# Aq1A_Guppy.net
KiCad netlist of a schematic drawn in Altium Designer
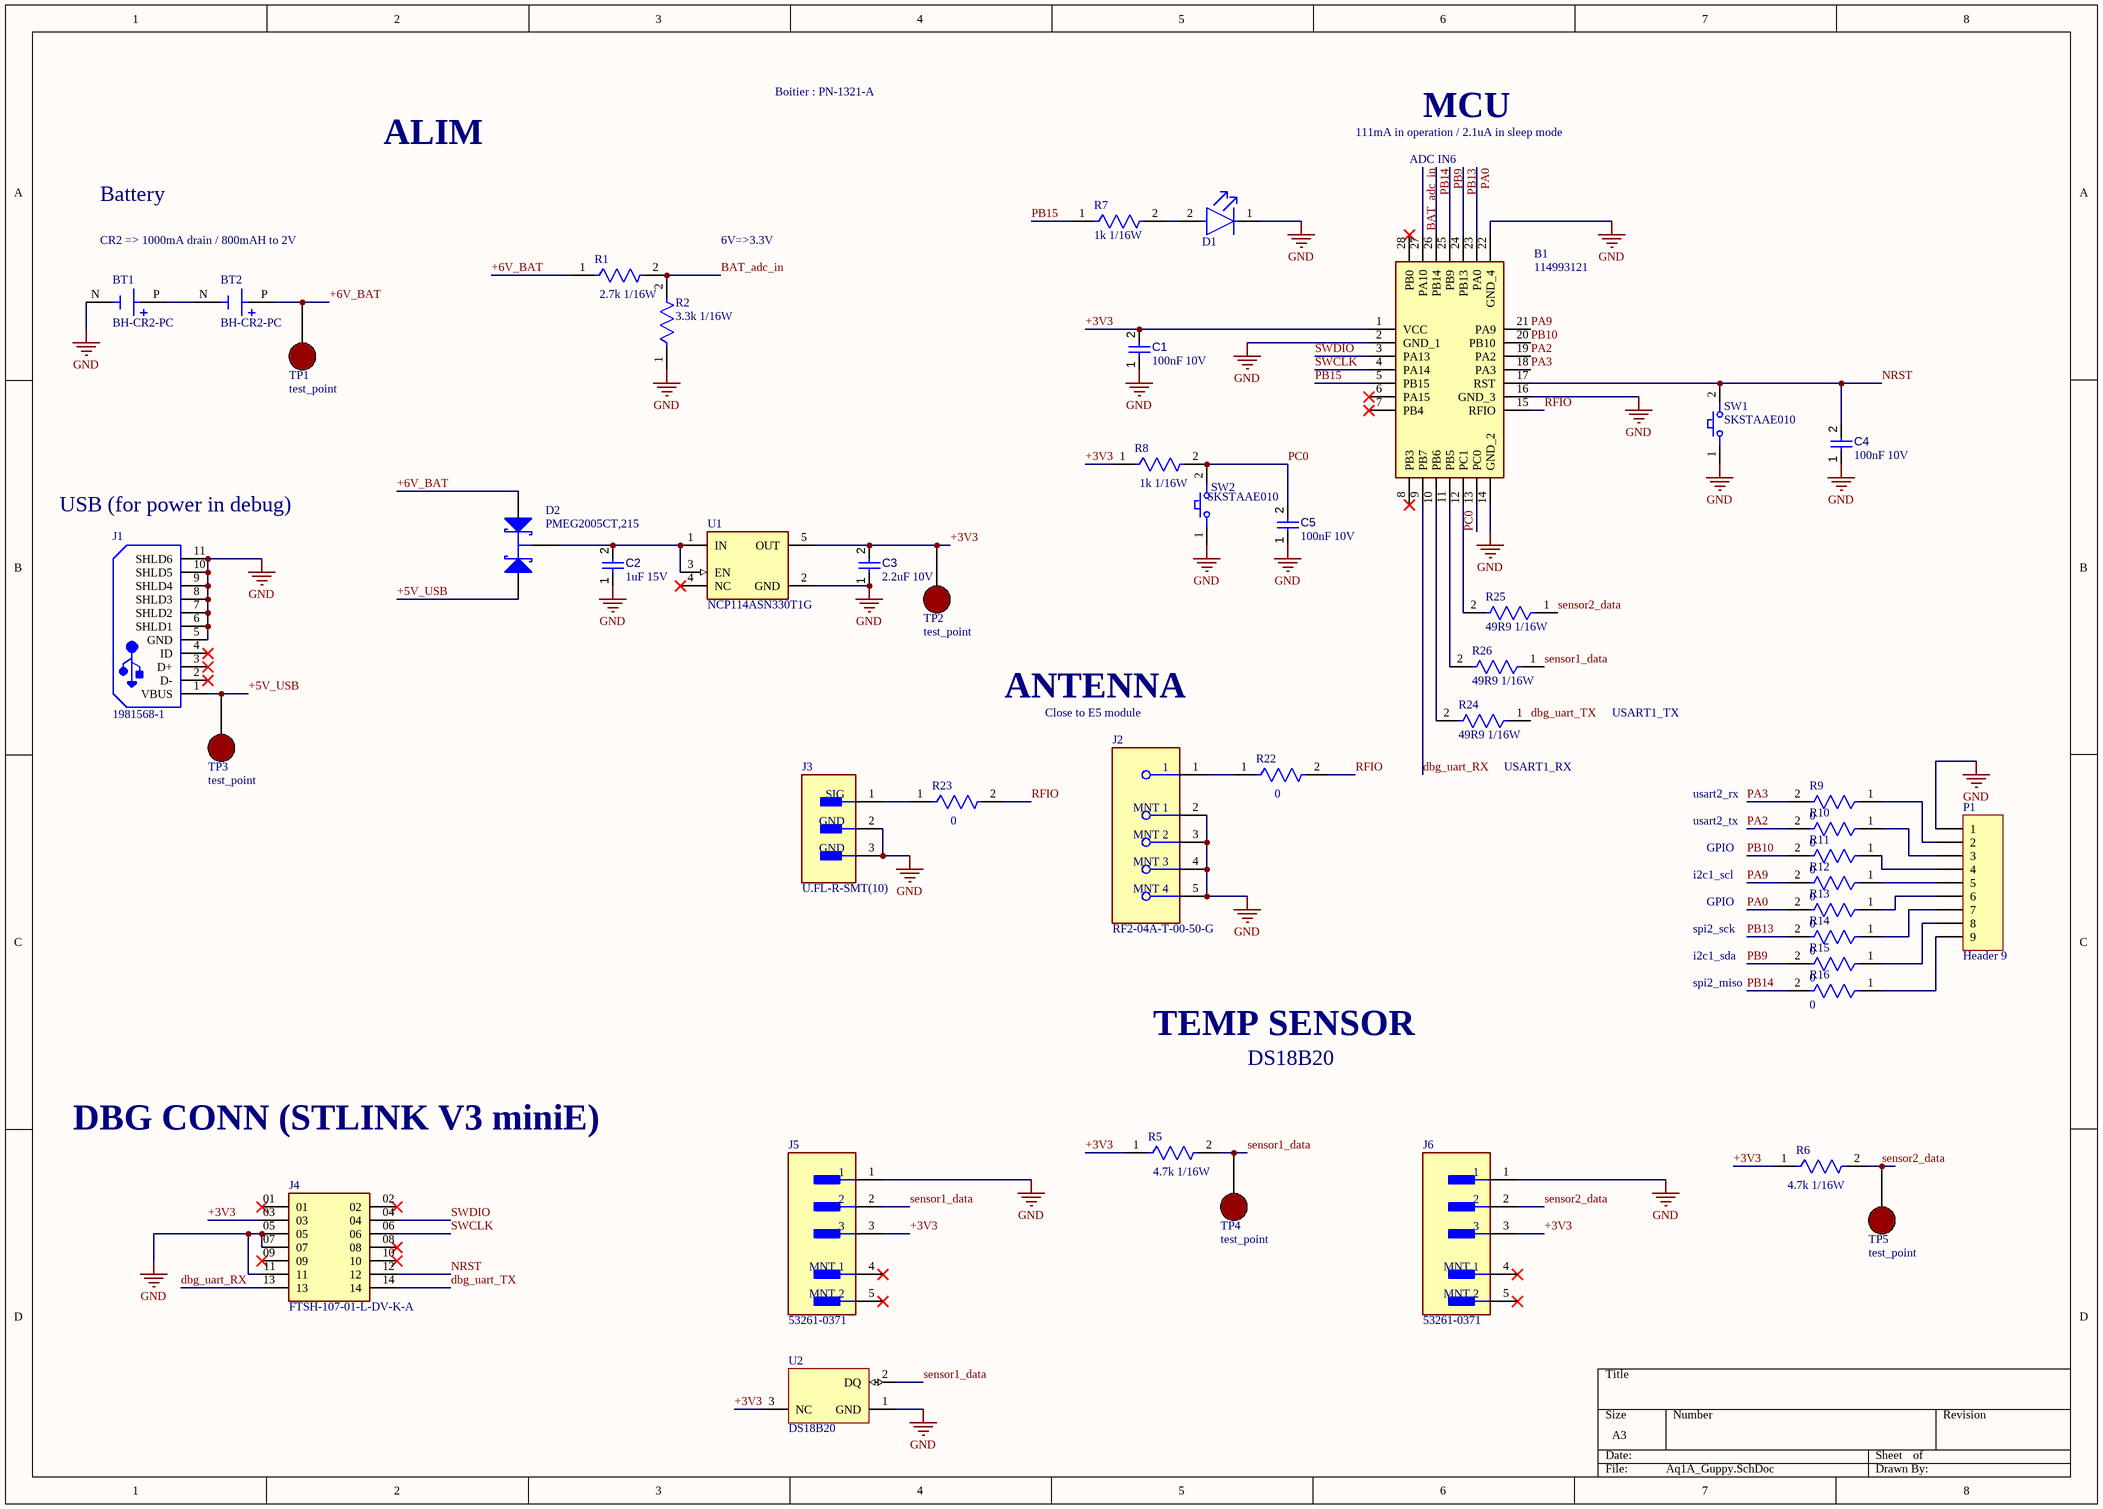
[diagram p0: Aq1A_Guppy.SchDoc]

(export (version "E")
  (design (tool "Eeschema 10.0.6"))
  (components
    (comp (ref "B1")
      (value "114993121")
      (footprint "114993121")
      (description "General ISM < 1GHz LoRaWAN Transceiver Module 868MHz, 915MHz Antenna Not Included Surface Mount")
      (fields (field (name "MOUSER PART NUMBER") "713-114993121"))
      (libsource (lib "LoraE5") (part "114993121"))
    )
    (comp (ref "BT1")
      (value "BH-CR2-PC")
      (footprint "BAT_BH-CR2-PC:BAT_BH-CR2-PC")
      (description "BATTERY HOLDER CR2 PC PIN")
      (fields (field (name "MF") "MPD"))
      (libsource (lib "BH-CR2-PC") (part "BH-CR2-PC"))
    )
    (comp (ref "BT2")
      (value "BH-CR2-PC")
      (footprint "BAT_BH-CR2-PC:BAT_BH-CR2-PC")
      (description "BATTERY HOLDER CR2 PC PIN")
      (fields (field (name "MF") "MPD"))
      (libsource (lib "BH-CR2-PC") (part "BH-CR2-PC"))
    )
    (comp (ref "C1")
      (value "100nF 10V")
      (footprint "CAPC2013X95X50LL10T25")
      (description "Chip Capacitor, 100 nF, +/- 10%, 50 V, 0805 (2012 Metric)")
      (fields (field (name "TOLERANCE") "10%") (field (name "Comment") "Capacitor 100 nF +/-10% 50 V 0805"))
      (libsource (lib "Samuel Grall") (part "CAP-NP-2"))
    )
    (comp (ref "C2")
      (value "1uF 15V")
      (footprint "CAPC2013X95X50LL10T25")
      (description "Chip Capacitor, 100 nF, +/- 10%, 50 V, 0805 (2012 Metric)")
      (fields (field (name "TOLERANCE") "10%") (field (name "Comment") "Capacitor 100 nF +/-10% 50 V 0805"))
      (libsource (lib "Samuel Grall") (part "CAP-NP-2"))
    )
    (comp (ref "C3")
      (value "2.2uF 10V")
      (footprint "CAPC2013X95X50LL10T25")
      (description "Chip Capacitor, 100 nF, +/- 10%, 50 V, 0805 (2012 Metric)")
      (fields (field (name "TOLERANCE") "10%") (field (name "Comment") "Capacitor 100 nF +/-10% 50 V 0805"))
      (libsource (lib "Samuel Grall") (part "CAP-NP-2"))
    )
    (comp (ref "C4")
      (value "100nF 10V")
      (footprint "CAPC2013X95X50LL10T25")
      (description "Chip Capacitor, 100 nF, +/- 10%, 50 V, 0805 (2012 Metric)")
      (fields (field (name "TOLERANCE") "10%") (field (name "Comment") "Capacitor 100 nF +/-10% 50 V 0805"))
      (libsource (lib "Samuel Grall") (part "CAP-NP-2"))
    )
    (comp (ref "C5")
      (value "100nF 10V")
      (footprint "CAPC2013X95X50LL10T25")
      (description "Chip Capacitor, 100 nF, +/- 10%, 50 V, 0805 (2012 Metric)")
      (fields (field (name "TOLERANCE") "10%") (field (name "Comment") "Capacitor 100 nF +/-10% 50 V 0805"))
      (libsource (lib "Samuel Grall") (part "CAP-NP-2"))
    )
    (comp (ref "D1")
      (value "SML-D12V8WT86C")
      (footprint "FP-SML-D12-MFG")
      (description "LED RED 1608 SMD")
      (libsource (lib "Altium Content Vault") (part "8706943c75ba83719d021d2fdc84c58"))
    )
    (comp (ref "D2")
      (value "PMEG2005CT,215")
      (footprint "STM-BAT54CFILM-3_V")
      (description "Small Signal Schottky Diode, 40 V, -40 to 150 degC, 3-Pin SOT23, RoHS, Tape and Reel")
      (fields (field (name "MANUFACTURER") "STMicroelectronics"))
      (libsource (lib "Altium Content Vault") (part "DSKY-AAK-3"))
    )
    (comp (ref "J1")
      (value "1981568-1")
      (footprint "TECO-1981568-5_V")
      (description "Micro USB Receptacle Standard Type B Assy, 5-Pin SMD, RoHS, Tape and Reel")
      (fields (field (name "MANUFACTURER") "TE Connectivity"))
      (libsource (lib "Altium Content Vault") (part "USB-5-6SHLD"))
    )
    (comp (ref "J2")
      (value "RF2-04A-T-00-50-G")
      (footprint "FP-RF2-04A-T-00-50-G-MFG")
      (description "CONN SMA JACK STR 50 OHM PCB")
      (libsource (lib "Altium Content Vault") (part "c65b8a639cdaef1819ea20b5466f8fa"))
    )
    (comp (ref "J3")
      (value "U.FL-R-SMT(10)")
      (footprint "FP-U_FL-R-SMT_10-MFG")
      (description "CONN U.FL RCPT STR 50 OHM SMD")
      (libsource (lib "Altium Content Vault") (part "eef6fde44c591823e8076210edfe12f"))
    )
    (comp (ref "J4")
      (value "FTSH-107-01-L-DV-K-A")
      (footprint "SAMTEC_FTSH-107-01-L-DV-K-A")
      (description "Connector Header Surface Mount 14 position 0.050 (1.27mm)")
      (fields (field (name "MF") "Samtec Inc."))
      (libsource (lib "FTSH-107-01-L-DV-K-A") (part "FTSH-107-01-L-DV-K-A"))
    )
    (comp (ref "J5")
      (value "53261-0371")
      (footprint "FP-53261-0371-MFG")
      (description "CONN HEADER SMD R/A 3POS 1.25MM")
      (fields
        (field (name "MANUFACTURER") "Molex")
        (field (name "OCTOPART") "https://octopart.com/53261-0371-molex-655314")
      )
      (libsource (lib "Altium Content Vault") (part "13850a6865a90496d8e6d51657cef87"))
    )
    (comp (ref "J6")
      (value "53261-0371")
      (footprint "FP-53261-0371-MFG")
      (description "CONN HEADER SMD R/A 3POS 1.25MM")
      (fields
        (field (name "MANUFACTURER") "Molex")
        (field (name "OCTOPART") "https://octopart.com/53261-0371-molex-655314")
      )
      (libsource (lib "Altium Content Vault") (part "13850a6865a90496d8e6d51657cef87"))
    )
    (comp (ref "P1")
      (value "Header 9")
      (footprint "HDR1X9")
      (description "Header, 9-Pin")
      (fields (field (name "PUBLISHER") "Altium Limited"))
      (libsource (lib "Miscellaneous Connectors") (part "Header 9"))
    )
    (comp (ref "R1")
      (value "2.7k 1/16W")
      (footprint "FP-HCJ0805-MFG")
      (description "RES 0 OHM JUMPER 1/2W 0805")
      (libsource (lib "Altium Content Vault") (part "1029c3af85768c4190bb7ad29bc67b5"))
    )
    (comp (ref "R2")
      (value "3.3k 1/16W")
      (footprint "FP-HCJ0805-MFG")
      (description "RES 0 OHM JUMPER 1/2W 0805")
      (libsource (lib "Altium Content Vault") (part "1029c3af85768c4190bb7ad29bc67b5"))
    )
    (comp (ref "R5")
      (value "4.7k 1/16W")
      (footprint "FP-HCJ0805-MFG")
      (description "RES 0 OHM JUMPER 1/2W 0805")
      (libsource (lib "Altium Content Vault") (part "1029c3af85768c4190bb7ad29bc67b5"))
    )
    (comp (ref "R6")
      (value "4.7k 1/16W")
      (footprint "FP-HCJ0805-MFG")
      (description "RES 0 OHM JUMPER 1/2W 0805")
      (libsource (lib "Altium Content Vault") (part "1029c3af85768c4190bb7ad29bc67b5"))
    )
    (comp (ref "R7")
      (value "1k 1/16W")
      (footprint "FP-HCJ0805-MFG")
      (description "RES 0 OHM JUMPER 1/2W 0805")
      (libsource (lib "Altium Content Vault") (part "1029c3af85768c4190bb7ad29bc67b5"))
    )
    (comp (ref "R8")
      (value "1k 1/16W")
      (footprint "FP-HCJ0805-MFG")
      (description "RES 0 OHM JUMPER 1/2W 0805")
      (libsource (lib "Altium Content Vault") (part "1029c3af85768c4190bb7ad29bc67b5"))
    )
    (comp (ref "R9")
      (value "0")
      (footprint "FP-HCJ0805-MFG")
      (description "RES 0 OHM JUMPER 1/2W 0805")
      (libsource (lib "Altium Content Vault") (part "1029c3af85768c4190bb7ad29bc67b5"))
    )
    (comp (ref "R10")
      (value "0")
      (footprint "FP-HCJ0805-MFG")
      (description "RES 0 OHM JUMPER 1/2W 0805")
      (libsource (lib "Altium Content Vault") (part "1029c3af85768c4190bb7ad29bc67b5"))
    )
    (comp (ref "R11")
      (value "0")
      (footprint "FP-HCJ0805-MFG")
      (description "RES 0 OHM JUMPER 1/2W 0805")
      (libsource (lib "Altium Content Vault") (part "1029c3af85768c4190bb7ad29bc67b5"))
    )
    (comp (ref "R12")
      (value "0")
      (footprint "FP-HCJ0805-MFG")
      (description "RES 0 OHM JUMPER 1/2W 0805")
      (libsource (lib "Altium Content Vault") (part "1029c3af85768c4190bb7ad29bc67b5"))
    )
    (comp (ref "R13")
      (value "0")
      (footprint "FP-HCJ0805-MFG")
      (description "RES 0 OHM JUMPER 1/2W 0805")
      (libsource (lib "Altium Content Vault") (part "1029c3af85768c4190bb7ad29bc67b5"))
    )
    (comp (ref "R14")
      (value "0")
      (footprint "FP-HCJ0805-MFG")
      (description "RES 0 OHM JUMPER 1/2W 0805")
      (libsource (lib "Altium Content Vault") (part "1029c3af85768c4190bb7ad29bc67b5"))
    )
    (comp (ref "R15")
      (value "0")
      (footprint "FP-HCJ0805-MFG")
      (description "RES 0 OHM JUMPER 1/2W 0805")
      (libsource (lib "Altium Content Vault") (part "1029c3af85768c4190bb7ad29bc67b5"))
    )
    (comp (ref "R16")
      (value "0")
      (footprint "FP-HCJ0805-MFG")
      (description "RES 0 OHM JUMPER 1/2W 0805")
      (libsource (lib "Altium Content Vault") (part "1029c3af85768c4190bb7ad29bc67b5"))
    )
    (comp (ref "R22")
      (value "0")
      (footprint "FP-HCJ0805-MFG")
      (description "RES 0 OHM JUMPER 1/2W 0805")
      (libsource (lib "Altium Content Vault") (part "1029c3af85768c4190bb7ad29bc67b5"))
    )
    (comp (ref "R23")
      (value "0")
      (footprint "FP-HCJ0805-MFG")
      (description "RES 0 OHM JUMPER 1/2W 0805")
      (libsource (lib "Altium Content Vault") (part "1029c3af85768c4190bb7ad29bc67b5"))
    )
    (comp (ref "R24")
      (value "49R9 1/16W")
      (footprint "FP-HCJ0805-MFG")
      (description "RES 0 OHM JUMPER 1/2W 0805")
      (libsource (lib "Altium Content Vault") (part "1029c3af85768c4190bb7ad29bc67b5"))
    )
    (comp (ref "R25")
      (value "49R9 1/16W")
      (footprint "FP-HCJ0805-MFG")
      (description "RES 0 OHM JUMPER 1/2W 0805")
      (libsource (lib "Altium Content Vault") (part "1029c3af85768c4190bb7ad29bc67b5"))
    )
    (comp (ref "R26")
      (value "49R9 1/16W")
      (footprint "FP-HCJ0805-MFG")
      (description "RES 0 OHM JUMPER 1/2W 0805")
      (libsource (lib "Altium Content Vault") (part "1029c3af85768c4190bb7ad29bc67b5"))
    )
    (comp (ref "SW1")
      (value "SKSTAAE010")
      (footprint "FP-SKSTAAE010-MFG")
      (description "Tactile Switches Quiet 0.9mm Middle Stroke, 4N,500KCycle")
      (libsource (lib "Altium Content Vault") (part "69e8347f6a24c021ef43a914a4df441"))
    )
    (comp (ref "SW2")
      (value "SKSTAAE010")
      (footprint "FP-SKSTAAE010-MFG")
      (description "Tactile Switches Quiet 0.9mm Middle Stroke, 4N,500KCycle")
      (libsource (lib "Altium Content Vault") (part "69e8347f6a24c021ef43a914a4df441"))
    )
    (comp (ref "TP1")
      (value "test_point")
      (footprint "test_point")
      (libsource (lib "test_point") (part "test_point"))
    )
    (comp (ref "TP2")
      (value "test_point")
      (footprint "test_point")
      (libsource (lib "test_point") (part "test_point"))
    )
    (comp (ref "TP3")
      (value "test_point")
      (footprint "test_point")
      (libsource (lib "test_point") (part "test_point"))
    )
    (comp (ref "TP4")
      (value "test_point")
      (footprint "test_point")
      (libsource (lib "test_point") (part "test_point"))
    )
    (comp (ref "TP5")
      (value "test_point")
      (footprint "test_point")
      (libsource (lib "test_point") (part "test_point"))
    )
    (comp (ref "U1")
      (value "NCP114ASN330T1G")
      (footprint "FP-483-MFG")
      (description "IC REG LINEAR 3.3V 300MA 5TSOP")
      (fields
        (field (name "MANUFACTURER") "ON Semiconductor")
        (field (name "OCTOPART") "https://octopart.com/ncp114asn330t1g-on+semiconductor-74628742")
      )
      (libsource (lib "Altium Content Vault") (part "57814aa37072aacea77ef0fe9350350"))
    )
    (comp (ref "U2")
      (value "DS18B20")
      (footprint "Q3+4")
      (libsource (lib "Altium Content Vault") (part "SEN-TEMP-DS1822-PAR-SIL3"))
    )
  )
  (nets
    (net (code "1") (name "/+3V3") (class "Default")
      (node (ref "B1") (pin "1") (pinfunction "VCC_1") (pintype "passive"))
      (node (ref "C1") (pin "2") (pinfunction "2_2") (pintype "passive"))
      (node (ref "C3") (pin "2") (pinfunction "2_2") (pintype "passive"))
      (node (ref "J4") (pin "03") (pinfunction "03_03") (pintype "passive"))
      (node (ref "J5") (pin "3") (pinfunction "3_3") (pintype "passive"))
      (node (ref "J6") (pin "3") (pinfunction "3_3") (pintype "passive"))
      (node (ref "R5") (pin "1") (pinfunction "1_1") (pintype "passive"))
      (node (ref "R6") (pin "1") (pinfunction "1_1") (pintype "passive"))
      (node (ref "R8") (pin "1") (pinfunction "1_1") (pintype "passive"))
      (node (ref "TP2") (pin "0") (pinfunction "0_0") (pintype "passive"))
      (node (ref "U1") (pin "5") (pinfunction "OUT_5") (pintype "power_in"))
      (node (ref "U2") (pin "3") (pinfunction "NC_3") (pintype "passive"))
    )
    (net (code "2") (name "/+5V_USB") (class "Default")
      (node (ref "D2") (pin "2") (pinfunction "A_2") (pintype "passive"))
      (node (ref "J1") (pin "1") (pinfunction "VBUS_1") (pintype "passive"))
      (node (ref "TP3") (pin "0") (pinfunction "0_0") (pintype "passive"))
    )
    (net (code "3") (name "/+6V_BAT") (class "Default")
      (node (ref "BT2") (pin "P") (pinfunction "POS_P") (pintype "passive"))
      (node (ref "D2") (pin "1") (pinfunction "A_1") (pintype "passive"))
      (node (ref "R1") (pin "1") (pinfunction "1_1") (pintype "passive"))
      (node (ref "TP1") (pin "0") (pinfunction "0_0") (pintype "passive"))
    )
    (net (code "4") (name "/BAT_adc_in") (class "Default")
      (node (ref "B1") (pin "27") (pinfunction "PA10_27") (pintype "passive"))
      (node (ref "R1") (pin "2") (pinfunction "2_2") (pintype "passive"))
      (node (ref "R2") (pin "2") (pinfunction "2_2") (pintype "passive"))
    )
    (net (code "5") (name "/NRST") (class "Default")
      (node (ref "B1") (pin "17") (pinfunction "RST_17") (pintype "passive"))
      (node (ref "C4") (pin "2") (pinfunction "2_2") (pintype "passive"))
      (node (ref "J4") (pin "12") (pinfunction "12_12") (pintype "passive"))
      (node (ref "SW1") (pin "2") (pinfunction "2_2") (pintype "passive"))
    )
    (net (code "6") (name "/PA0") (class "Default")
      (node (ref "B1") (pin "23") (pinfunction "PA0_23") (pintype "passive"))
      (node (ref "R13") (pin "2") (pinfunction "2_2") (pintype "passive"))
    )
    (net (code "7") (name "/PA2") (class "Default")
      (node (ref "B1") (pin "19") (pinfunction "PA2_19") (pintype "passive"))
      (node (ref "R10") (pin "2") (pinfunction "2_2") (pintype "passive"))
    )
    (net (code "8") (name "/PA3") (class "Default")
      (node (ref "B1") (pin "18") (pinfunction "PA3_18") (pintype "passive"))
      (node (ref "R9") (pin "2") (pinfunction "2_2") (pintype "passive"))
    )
    (net (code "9") (name "/PA9") (class "Default")
      (node (ref "B1") (pin "21") (pinfunction "PA9_21") (pintype "passive"))
      (node (ref "R12") (pin "2") (pinfunction "2_2") (pintype "passive"))
    )
    (net (code "10") (name "/PB9") (class "Default")
      (node (ref "B1") (pin "25") (pinfunction "PB9_25") (pintype "passive"))
      (node (ref "R15") (pin "2") (pinfunction "2_2") (pintype "passive"))
    )
    (net (code "11") (name "/PB10") (class "Default")
      (node (ref "B1") (pin "20") (pinfunction "PB10_20") (pintype "passive"))
      (node (ref "R11") (pin "2") (pinfunction "2_2") (pintype "passive"))
    )
    (net (code "12") (name "/PB13") (class "Default")
      (node (ref "B1") (pin "24") (pinfunction "PB13_24") (pintype "passive"))
      (node (ref "R14") (pin "2") (pinfunction "2_2") (pintype "passive"))
    )
    (net (code "13") (name "/PB14") (class "Default")
      (node (ref "B1") (pin "26") (pinfunction "PB14_26") (pintype "passive"))
      (node (ref "R16") (pin "2") (pinfunction "2_2") (pintype "passive"))
    )
    (net (code "14") (name "/PB15") (class "Default")
      (node (ref "B1") (pin "5") (pinfunction "PB15_5") (pintype "passive"))
      (node (ref "R7") (pin "1") (pinfunction "1_1") (pintype "passive"))
    )
    (net (code "15") (name "/PC0") (class "Default")
      (node (ref "B1") (pin "13") (pinfunction "PC0_13") (pintype "passive"))
      (node (ref "C5") (pin "2") (pinfunction "2_2") (pintype "passive"))
      (node (ref "R8") (pin "2") (pinfunction "2_2") (pintype "passive"))
      (node (ref "SW2") (pin "2") (pinfunction "2_2") (pintype "passive"))
    )
    (net (code "16") (name "/RFIO") (class "Default")
      (node (ref "B1") (pin "15") (pinfunction "RFIO_15") (pintype "passive"))
      (node (ref "R22") (pin "2") (pinfunction "2_2") (pintype "passive"))
      (node (ref "R23") (pin "2") (pinfunction "2_2") (pintype "passive"))
    )
    (net (code "17") (name "/SWCLK") (class "Default")
      (node (ref "B1") (pin "4") (pinfunction "PA14_4") (pintype "passive"))
      (node (ref "J4") (pin "06") (pinfunction "06_06") (pintype "passive"))
    )
    (net (code "18") (name "/SWDIO") (class "Default")
      (node (ref "B1") (pin "3") (pinfunction "PA13_3") (pintype "passive"))
      (node (ref "J4") (pin "04") (pinfunction "04_04") (pintype "passive"))
    )
    (net (code "19") (name "/dbg_uart_RX") (class "Default")
      (node (ref "B1") (pin "9") (pinfunction "PB7_9") (pintype "passive"))
      (node (ref "J4") (pin "13") (pinfunction "13_13") (pintype "passive"))
    )
    (net (code "20") (name "/dbg_uart_TX") (class "Default")
      (node (ref "J4") (pin "14") (pinfunction "14_14") (pintype "passive"))
      (node (ref "R24") (pin "1") (pinfunction "1_1") (pintype "passive"))
    )
    (net (code "21") (name "/sensor1_data") (class "Default")
      (node (ref "J5") (pin "2") (pinfunction "2_2") (pintype "passive"))
      (node (ref "R26") (pin "1") (pinfunction "1_1") (pintype "passive"))
      (node (ref "R5") (pin "2") (pinfunction "2_2") (pintype "passive"))
      (node (ref "TP4") (pin "0") (pinfunction "0_0") (pintype "passive"))
      (node (ref "U2") (pin "2") (pinfunction "DQ_2") (pintype "bidirectional"))
    )
    (net (code "22") (name "/sensor2_data") (class "Default")
      (node (ref "J6") (pin "2") (pinfunction "2_2") (pintype "passive"))
      (node (ref "R25") (pin "1") (pinfunction "1_1") (pintype "passive"))
      (node (ref "R6") (pin "2") (pinfunction "2_2") (pintype "passive"))
      (node (ref "TP5") (pin "0") (pinfunction "0_0") (pintype "passive"))
    )
    (net (code "23") (name "GND") (class "Default")
      (node (ref "B1") (pin "14") (pinfunction "GND_2_14") (pintype "passive"))
      (node (ref "B1") (pin "16") (pinfunction "GND_3_16") (pintype "passive"))
      (node (ref "B1") (pin "2") (pinfunction "GND_1_2") (pintype "passive"))
      (node (ref "B1") (pin "22") (pinfunction "GND_4_22") (pintype "passive"))
      (node (ref "BT1") (pin "N") (pinfunction "NEG_N") (pintype "passive"))
      (node (ref "C1") (pin "1") (pinfunction "1_1") (pintype "passive"))
      (node (ref "C2") (pin "1") (pinfunction "1_1") (pintype "passive"))
      (node (ref "C3") (pin "1") (pinfunction "1_1") (pintype "passive"))
      (node (ref "C4") (pin "1") (pinfunction "1_1") (pintype "passive"))
      (node (ref "C5") (pin "1") (pinfunction "1_1") (pintype "passive"))
      (node (ref "D1") (pin "1") (pinfunction "C_1") (pintype "passive"))
      (node (ref "J1") (pin "10") (pinfunction "SHLD5_10") (pintype "passive"))
      (node (ref "J1") (pin "11") (pinfunction "SHLD6_11") (pintype "passive"))
      (node (ref "J1") (pin "5") (pinfunction "GND_5") (pintype "passive"))
      (node (ref "J1") (pin "6") (pinfunction "SHLD1_6") (pintype "passive"))
      (node (ref "J1") (pin "7") (pinfunction "SHLD2_7") (pintype "passive"))
      (node (ref "J1") (pin "8") (pinfunction "SHLD3_8") (pintype "passive"))
      (node (ref "J1") (pin "9") (pinfunction "SHLD4_9") (pintype "passive"))
      (node (ref "J2") (pin "2") (pinfunction "MNT_1_2") (pintype "passive"))
      (node (ref "J2") (pin "3") (pinfunction "MNT_2_3") (pintype "passive"))
      (node (ref "J2") (pin "4") (pinfunction "MNT_3_4") (pintype "passive"))
      (node (ref "J2") (pin "5") (pinfunction "MNT_4_5") (pintype "passive"))
      (node (ref "J3") (pin "2") (pinfunction "GND_2") (pintype "power_in"))
      (node (ref "J3") (pin "3") (pinfunction "GND_3") (pintype "power_in"))
      (node (ref "J4") (pin "05") (pinfunction "05_05") (pintype "passive"))
      (node (ref "J4") (pin "07") (pinfunction "07_07") (pintype "passive"))
      (node (ref "J4") (pin "11") (pinfunction "11_11") (pintype "passive"))
      (node (ref "J5") (pin "1") (pinfunction "1_1") (pintype "passive"))
      (node (ref "J6") (pin "1") (pinfunction "1_1") (pintype "passive"))
      (node (ref "P1") (pin "1") (pinfunction "1_1") (pintype "passive"))
      (node (ref "R2") (pin "1") (pinfunction "1_1") (pintype "passive"))
      (node (ref "SW1") (pin "1") (pinfunction "1_1") (pintype "passive"))
      (node (ref "SW2") (pin "1") (pinfunction "1_1") (pintype "passive"))
      (node (ref "U1") (pin "2") (pinfunction "GND_2") (pintype "power_in"))
      (node (ref "U2") (pin "1") (pinfunction "GND_1") (pintype "power_in"))
    )
    (net (code "24") (name "Net-(B1-PB5)") (class "Default")
      (node (ref "B1") (pin "11") (pinfunction "PB5_11") (pintype "passive"))
      (node (ref "R26") (pin "2") (pinfunction "2_2") (pintype "passive"))
    )
    (net (code "25") (name "Net-(B1-PB6)") (class "Default")
      (node (ref "B1") (pin "10") (pinfunction "PB6_10") (pintype "passive"))
      (node (ref "R24") (pin "2") (pinfunction "2_2") (pintype "passive"))
    )
    (net (code "26") (name "Net-(B1-PC1)") (class "Default")
      (node (ref "B1") (pin "12") (pinfunction "PC1_12") (pintype "passive"))
      (node (ref "R25") (pin "2") (pinfunction "2_2") (pintype "passive"))
    )
    (net (code "27") (name "Net-(BT1-POS)") (class "Default")
      (node (ref "BT1") (pin "P") (pinfunction "POS_P") (pintype "passive"))
      (node (ref "BT2") (pin "N") (pinfunction "NEG_N") (pintype "passive"))
    )
    (net (code "28") (name "Net-(D1-A)") (class "Default")
      (node (ref "D1") (pin "2") (pinfunction "A_2") (pintype "passive"))
      (node (ref "R7") (pin "2") (pinfunction "2_2") (pintype "passive"))
    )
    (net (code "29") (name "Net-(D2-K)") (class "Default")
      (node (ref "C2") (pin "2") (pinfunction "2_2") (pintype "passive"))
      (node (ref "D2") (pin "3") (pinfunction "K_3") (pintype "passive"))
      (node (ref "U1") (pin "1") (pinfunction "IN_1") (pintype "power_in"))
      (node (ref "U1") (pin "3") (pinfunction "EN_3") (pintype "input"))
    )
    (net (code "30") (name "Net-(J2-Pad1)") (class "Default")
      (node (ref "J2") (pin "1") (pinfunction "1_1") (pintype "passive"))
      (node (ref "R22") (pin "1") (pinfunction "1_1") (pintype "passive"))
    )
    (net (code "31") (name "Net-(J3-SIG)") (class "Default")
      (node (ref "J3") (pin "1") (pinfunction "SIG_1") (pintype "passive"))
      (node (ref "R23") (pin "1") (pinfunction "1_1") (pintype "passive"))
    )
    (net (code "32") (name "Net-(P1-Pad2)") (class "Default")
      (node (ref "P1") (pin "2") (pinfunction "2_2") (pintype "passive"))
      (node (ref "R9") (pin "1") (pinfunction "1_1") (pintype "passive"))
    )
    (net (code "33") (name "Net-(P1-Pad3)") (class "Default")
      (node (ref "P1") (pin "3") (pinfunction "3_3") (pintype "passive"))
      (node (ref "R10") (pin "1") (pinfunction "1_1") (pintype "passive"))
    )
    (net (code "34") (name "Net-(P1-Pad4)") (class "Default")
      (node (ref "P1") (pin "4") (pinfunction "4_4") (pintype "passive"))
      (node (ref "R11") (pin "1") (pinfunction "1_1") (pintype "passive"))
    )
    (net (code "35") (name "Net-(P1-Pad5)") (class "Default")
      (node (ref "P1") (pin "5") (pinfunction "5_5") (pintype "passive"))
      (node (ref "R12") (pin "1") (pinfunction "1_1") (pintype "passive"))
    )
    (net (code "36") (name "Net-(P1-Pad6)") (class "Default")
      (node (ref "P1") (pin "6") (pinfunction "6_6") (pintype "passive"))
      (node (ref "R13") (pin "1") (pinfunction "1_1") (pintype "passive"))
    )
    (net (code "37") (name "Net-(P1-Pad7)") (class "Default")
      (node (ref "P1") (pin "7") (pinfunction "7_7") (pintype "passive"))
      (node (ref "R14") (pin "1") (pinfunction "1_1") (pintype "passive"))
    )
    (net (code "38") (name "Net-(P1-Pad8)") (class "Default")
      (node (ref "P1") (pin "8") (pinfunction "8_8") (pintype "passive"))
      (node (ref "R15") (pin "1") (pinfunction "1_1") (pintype "passive"))
    )
    (net (code "39") (name "Net-(P1-Pad9)") (class "Default")
      (node (ref "P1") (pin "9") (pinfunction "9_9") (pintype "passive"))
      (node (ref "R16") (pin "1") (pinfunction "1_1") (pintype "passive"))
    )
    (net (code "40") (name "unconnected-(B1-PA15-Pad6)") (class "Default")
      (node (ref "B1") (pin "6") (pinfunction "PA15_6") (pintype "passive+no_connect"))
    )
    (net (code "41") (name "unconnected-(B1-PB0-Pad28)") (class "Default")
      (node (ref "B1") (pin "28") (pinfunction "PB0_28") (pintype "passive+no_connect"))
    )
    (net (code "42") (name "unconnected-(B1-PB3-Pad8)") (class "Default")
      (node (ref "B1") (pin "8") (pinfunction "PB3_8") (pintype "passive+no_connect"))
    )
    (net (code "43") (name "unconnected-(B1-PB4-Pad7)") (class "Default")
      (node (ref "B1") (pin "7") (pinfunction "PB4_7") (pintype "passive+no_connect"))
    )
    (net (code "44") (name "unconnected-(J1-D+-Pad3)") (class "Default")
      (node (ref "J1") (pin "3") (pinfunction "D+_3") (pintype "passive+no_connect"))
    )
    (net (code "45") (name "unconnected-(J1-D--Pad2)") (class "Default")
      (node (ref "J1") (pin "2") (pinfunction "D-_2") (pintype "passive+no_connect"))
    )
    (net (code "46") (name "unconnected-(J1-ID-Pad4)") (class "Default")
      (node (ref "J1") (pin "4") (pinfunction "ID_4") (pintype "passive+no_connect"))
    )
    (net (code "47") (name "unconnected-(J4-Pad01)") (class "Default")
      (node (ref "J4") (pin "01") (pinfunction "01_01") (pintype "passive+no_connect"))
    )
    (net (code "48") (name "unconnected-(J4-Pad02)") (class "Default")
      (node (ref "J4") (pin "02") (pinfunction "02_02") (pintype "passive+no_connect"))
    )
    (net (code "49") (name "unconnected-(J4-Pad08)") (class "Default")
      (node (ref "J4") (pin "08") (pinfunction "08_08") (pintype "passive+no_connect"))
    )
    (net (code "50") (name "unconnected-(J4-Pad09)") (class "Default")
      (node (ref "J4") (pin "09") (pinfunction "09_09") (pintype "passive+no_connect"))
    )
    (net (code "51") (name "unconnected-(J4-Pad10)") (class "Default")
      (node (ref "J4") (pin "10") (pinfunction "10_10") (pintype "passive+no_connect"))
    )
    (net (code "52") (name "unconnected-(J5-MNT_1-Pad4)") (class "Default")
      (node (ref "J5") (pin "4") (pinfunction "MNT_1_4") (pintype "passive+no_connect"))
    )
    (net (code "53") (name "unconnected-(J5-MNT_2-Pad5)") (class "Default")
      (node (ref "J5") (pin "5") (pinfunction "MNT_2_5") (pintype "passive+no_connect"))
    )
    (net (code "54") (name "unconnected-(J6-MNT_1-Pad4)") (class "Default")
      (node (ref "J6") (pin "4") (pinfunction "MNT_1_4") (pintype "passive+no_connect"))
    )
    (net (code "55") (name "unconnected-(J6-MNT_2-Pad5)") (class "Default")
      (node (ref "J6") (pin "5") (pinfunction "MNT_2_5") (pintype "passive+no_connect"))
    )
    (net (code "56") (name "unconnected-(U1-NC-Pad4)") (class "Default")
      (node (ref "U1") (pin "4") (pinfunction "NC_4") (pintype "passive+no_connect"))
    )
  )
)
